# hot_spring.net
KiCad netlist of a schematic drawn in EAGLE
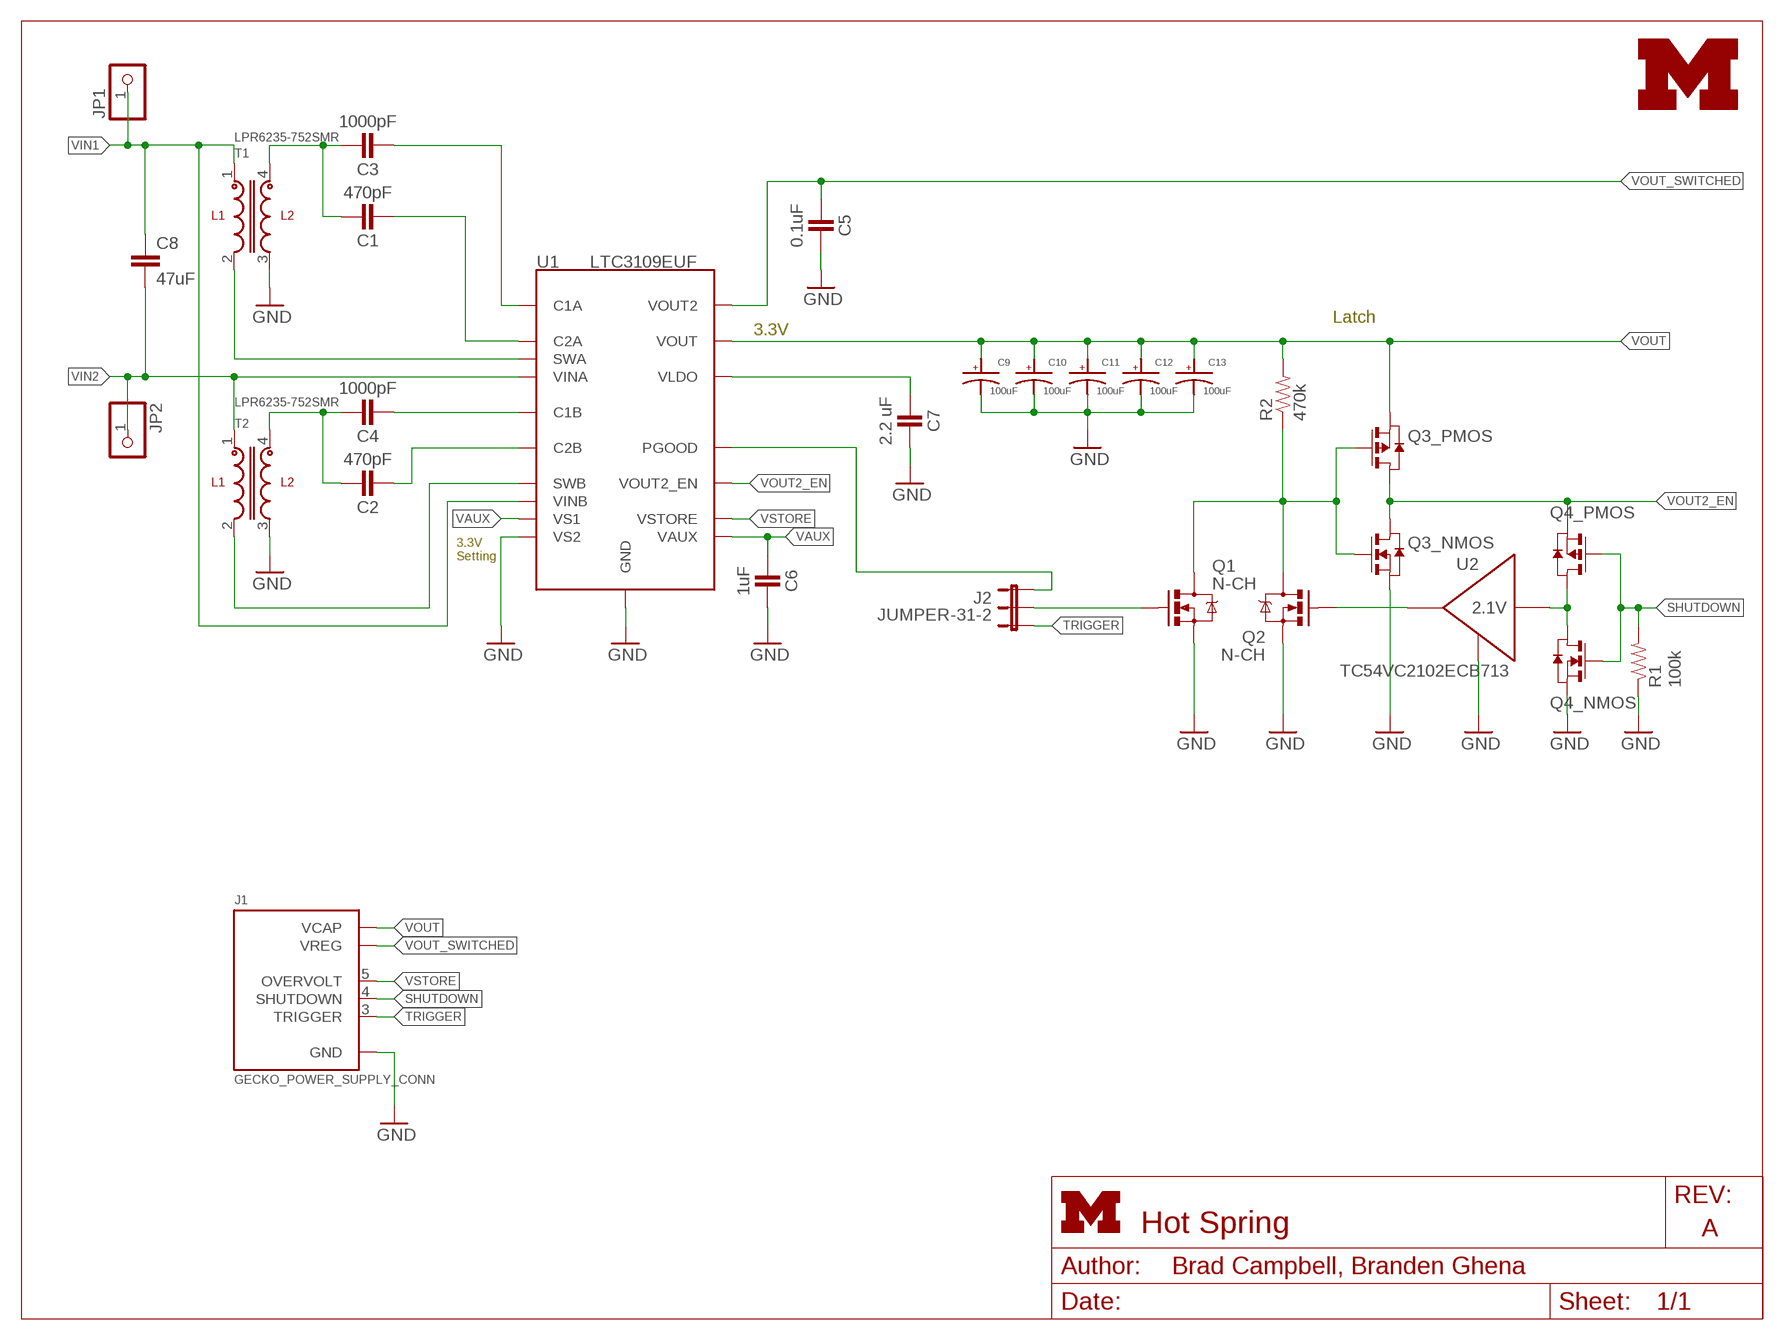
[diagram p0: schematic, sheet 1]

(export (version "E")
  (design (tool "Eeschema 10.0.6"))
  (components
    (comp (ref "C1")
      (value "470pF")
      (footprint "eagle-import:0402_CAP")
      (libsource (lib "eagle-import") (part "CAPACITOR"))
    )
    (comp (ref "C2")
      (value "470pF")
      (footprint "eagle-import:0402_CAP")
      (libsource (lib "eagle-import") (part "CAPACITOR"))
    )
    (comp (ref "C3")
      (value "1000pF")
      (footprint "eagle-import:0402_CAP")
      (libsource (lib "eagle-import") (part "CAPACITOR"))
    )
    (comp (ref "C4")
      (value "1000pF")
      (footprint "eagle-import:0402_CAP")
      (libsource (lib "eagle-import") (part "CAPACITOR"))
    )
    (comp (ref "C5")
      (value "0.1uF")
      (footprint "eagle-import:0402_CAP")
      (libsource (lib "eagle-import") (part "CAPACITOR"))
    )
    (comp (ref "C6")
      (value "1uF")
      (footprint "eagle-import:0402_CAP")
      (libsource (lib "eagle-import") (part "CAPACITOR"))
    )
    (comp (ref "C7")
      (value "2.2 uF")
      (footprint "eagle-import:0402_CAP")
      (libsource (lib "eagle-import") (part "CAPACITOR"))
    )
    (comp (ref "C8")
      (value "47uF")
      (footprint "eagle-import:1210")
      (libsource (lib "eagle-import") (part "CAP1210"))
    )
    (comp (ref "C9")
      (value "100uF")
      (footprint "eagle-import:CAP1210")
      (libsource (lib "eagle-import") (part "1210_CAP_POLARIZED"))
    )
    (comp (ref "C10")
      (value "100uF")
      (footprint "eagle-import:CAP1210")
      (libsource (lib "eagle-import") (part "1210_CAP_POLARIZED"))
    )
    (comp (ref "C11")
      (value "100uF")
      (footprint "eagle-import:CAP1210")
      (libsource (lib "eagle-import") (part "1210_CAP_POLARIZED"))
    )
    (comp (ref "C12")
      (value "100uF")
      (footprint "eagle-import:CAP1210")
      (libsource (lib "eagle-import") (part "1210_CAP_POLARIZED"))
    )
    (comp (ref "C13")
      (value "100uF")
      (footprint "eagle-import:CAP1210")
      (libsource (lib "eagle-import") (part "1210_CAP_POLARIZED"))
    )
    (comp (ref "J1")
      (value "GECKO_POWER_SUPPLY_CONN")
      (footprint "eagle-import:HEADER1X6_0.05IN")
      (libsource (lib "eagle-import") (part "GECKO_POWER_SUPPLY_CONN"))
    )
    (comp (ref "J2")
      (value "JUMPER-31-2")
      (footprint "eagle-import:SJ_3_PASTE1&2")
      (libsource (lib "eagle-import") (part "JUMPER-31-2"))
    )
    (comp (ref "JP1")
      (value "PINHD-1X1")
      (footprint "eagle-import:1X01")
      (libsource (lib "eagle-import") (part "PINHD-1X1"))
    )
    (comp (ref "JP2")
      (value "PINHD-1X1")
      (footprint "eagle-import:1X01")
      (libsource (lib "eagle-import") (part "PINHD-1X1"))
    )
    (comp (ref "LOGO1")
      (value "UMICH_SOLID_SMALL")
      (footprint "eagle-import:UMICH_SOLID_75MIL")
      (libsource (lib "eagle-import") (part "UMICH_SOLID_SMALL"))
    )
    (comp (ref "Q1")
      (value "MOSFET-NCHANNELSMD")
      (footprint "eagle-import:SOT23-3")
      (libsource (lib "eagle-import") (part "MOSFET-NCHANNELSMD"))
    )
    (comp (ref "Q2")
      (value "MOSFET-NCHANNELSMD")
      (footprint "eagle-import:SOT23-3")
      (libsource (lib "eagle-import") (part "MOSFET-NCHANNELSMD"))
    )
    (comp (ref "Q3")
      (value "DUAL_MOSFET_NP")
      (footprint "eagle-import:TSOP-6")
      (libsource (lib "eagle-import") (part "DUAL_MOSFET_NP"))
    )
    (comp (ref "Q4")
      (value "DUAL_MOSFET_NP")
      (footprint "eagle-import:TSOP-6")
      (libsource (lib "eagle-import") (part "DUAL_MOSFET_NP"))
    )
    (comp (ref "R1")
      (value "100k")
      (footprint "eagle-import:0402_RES")
      (libsource (lib "eagle-import") (part "RESISTOR0402_RES"))
    )
    (comp (ref "R2")
      (value "470k")
      (footprint "eagle-import:0402_RES")
      (libsource (lib "eagle-import") (part "RESISTOR0402_RES"))
    )
    (comp (ref "T1")
      (value "LPR6235-752SMR")
      (footprint "eagle-import:LPR6235")
      (libsource (lib "eagle-import") (part "LPR6235-752SMR"))
    )
    (comp (ref "T2")
      (value "LPR6235-752SMR")
      (footprint "eagle-import:LPR6235")
      (libsource (lib "eagle-import") (part "LPR6235-752SMR"))
    )
    (comp (ref "U1")
      (value "LTC3109EUF")
      (footprint "eagle-import:QFN-20-4MM")
      (libsource (lib "eagle-import") (part "LTC3109EUF"))
    )
    (comp (ref "U2")
      (value "TC54VC2102ECB713")
      (footprint "eagle-import:SOT-23")
      (libsource (lib "eagle-import") (part "TC54VC2102ECB713"))
    )
  )
  (nets
    (net (code "1") (name "GND") (class "Default")
      (node (ref "C10") (pin "ANODE") (pinfunction "ANODE_ANODE") (pintype "bidirectional"))
      (node (ref "C11") (pin "ANODE") (pinfunction "ANODE_ANODE") (pintype "bidirectional"))
      (node (ref "C12") (pin "ANODE") (pinfunction "ANODE_ANODE") (pintype "bidirectional"))
      (node (ref "C13") (pin "ANODE") (pinfunction "ANODE_ANODE") (pintype "bidirectional"))
      (node (ref "C5") (pin "1") (pinfunction "1_1") (pintype "bidirectional"))
      (node (ref "C6") (pin "1") (pinfunction "1_1") (pintype "bidirectional"))
      (node (ref "C7") (pin "1") (pinfunction "1_1") (pintype "bidirectional"))
      (node (ref "C9") (pin "ANODE") (pinfunction "ANODE_ANODE") (pintype "bidirectional"))
      (node (ref "J1") (pin "1") (pinfunction "GND_1") (pintype "bidirectional"))
      (node (ref "Q1") (pin "2") (pinfunction "S_2") (pintype "passive"))
      (node (ref "Q2") (pin "2") (pinfunction "S_2") (pintype "passive"))
      (node (ref "Q3") (pin "5") (pinfunction "S_5") (pintype "passive"))
      (node (ref "Q4") (pin "5") (pinfunction "S_5") (pintype "passive"))
      (node (ref "R1") (pin "1") (pinfunction "1_1") (pintype "passive"))
      (node (ref "T1") (pin "3") (pinfunction "3_3") (pintype "bidirectional"))
      (node (ref "T2") (pin "3") (pinfunction "3_3") (pintype "bidirectional"))
      (node (ref "U1") (pin "11") (pinfunction "GND_11") (pintype "bidirectional"))
      (node (ref "U1") (pin "16") (pinfunction "GND_16") (pintype "bidirectional"))
      (node (ref "U1") (pin "20") (pinfunction "VS2_20") (pintype "bidirectional"))
      (node (ref "U1") (pin "8") (pinfunction "GND_8") (pintype "bidirectional"))
      (node (ref "U1") (pin "GND") (pinfunction "GND_GND") (pintype "bidirectional"))
      (node (ref "U2") (pin "2") (pinfunction "GND_2") (pintype "bidirectional"))
    )
    (net (code "2") (name "Net-(C1-Pad1)") (class "Default")
      (node (ref "C1") (pin "1") (pinfunction "1_1") (pintype "bidirectional"))
      (node (ref "C3") (pin "1") (pinfunction "1_1") (pintype "bidirectional"))
      (node (ref "T1") (pin "4") (pinfunction "4_4") (pintype "bidirectional"))
    )
    (net (code "3") (name "Net-(C2-Pad1)") (class "Default")
      (node (ref "C2") (pin "1") (pinfunction "1_1") (pintype "bidirectional"))
      (node (ref "C4") (pin "1") (pinfunction "1_1") (pintype "bidirectional"))
      (node (ref "T2") (pin "4") (pinfunction "4_4") (pintype "bidirectional"))
    )
    (net (code "4") (name "Net-(Q1-D)") (class "Default")
      (node (ref "Q1") (pin "3") (pinfunction "D_3") (pintype "passive"))
      (node (ref "Q2") (pin "3") (pinfunction "D_3") (pintype "passive"))
      (node (ref "Q3") (pin "1") (pinfunction "G_1") (pintype "passive"))
      (node (ref "Q3") (pin "3") (pinfunction "G_3") (pintype "passive"))
      (node (ref "R2") (pin "1") (pinfunction "1_1") (pintype "passive"))
    )
    (net (code "5") (name "Net-(Q1-G)") (class "Default")
      (node (ref "J2") (pin "2") (pinfunction "2_2") (pintype "passive"))
      (node (ref "Q1") (pin "1") (pinfunction "G_1") (pintype "passive"))
    )
    (net (code "6") (name "Net-(Q2-G)") (class "Default")
      (node (ref "Q2") (pin "1") (pinfunction "G_1") (pintype "passive"))
      (node (ref "U2") (pin "1") (pinfunction "OUT_1") (pintype "bidirectional"))
    )
    (net (code "7") (name "Net-(Q4A-D)") (class "Default")
      (node (ref "Q4") (pin "4") (pinfunction "D_4") (pintype "passive"))
      (node (ref "Q4") (pin "6") (pinfunction "D_6") (pintype "passive"))
      (node (ref "U2") (pin "3") (pinfunction "IN_3") (pintype "bidirectional"))
    )
    (net (code "8") (name "Net-(U1-C1A)") (class "Default")
      (node (ref "C3") (pin "2") (pinfunction "2_2") (pintype "bidirectional"))
      (node (ref "U1") (pin "18") (pinfunction "C1A_18") (pintype "bidirectional"))
    )
    (net (code "9") (name "Net-(U1-C1B)") (class "Default")
      (node (ref "C4") (pin "2") (pinfunction "2_2") (pintype "bidirectional"))
      (node (ref "U1") (pin "9") (pinfunction "C1B_9") (pintype "bidirectional"))
    )
    (net (code "10") (name "Net-(U1-C2A)") (class "Default")
      (node (ref "C1") (pin "2") (pinfunction "2_2") (pintype "bidirectional"))
      (node (ref "U1") (pin "17") (pinfunction "C2A_17") (pintype "bidirectional"))
    )
    (net (code "11") (name "Net-(U1-C2B)") (class "Default")
      (node (ref "C2") (pin "2") (pinfunction "2_2") (pintype "bidirectional"))
      (node (ref "U1") (pin "10") (pinfunction "C2B_10") (pintype "bidirectional"))
    )
    (net (code "12") (name "Net-(U1-PGOOD)") (class "Default")
      (node (ref "J2") (pin "1") (pinfunction "1_1") (pintype "passive"))
      (node (ref "U1") (pin "6") (pinfunction "PGOOD_6") (pintype "bidirectional"))
    )
    (net (code "13") (name "Net-(U1-SWA)") (class "Default")
      (node (ref "T1") (pin "2") (pinfunction "2_2") (pintype "bidirectional"))
      (node (ref "U1") (pin "15") (pinfunction "SWA_15") (pintype "bidirectional"))
    )
    (net (code "14") (name "Net-(U1-SWB)") (class "Default")
      (node (ref "T2") (pin "2") (pinfunction "2_2") (pintype "bidirectional"))
      (node (ref "U1") (pin "12") (pinfunction "SWB_12") (pintype "bidirectional"))
    )
    (net (code "15") (name "Net-(U1-VLDO)") (class "Default")
      (node (ref "C7") (pin "2") (pinfunction "2_2") (pintype "bidirectional"))
      (node (ref "U1") (pin "7") (pinfunction "VLDO_7") (pintype "bidirectional"))
    )
    (net (code "16") (name "SHUTDOWN") (class "Default")
      (node (ref "J1") (pin "4") (pinfunction "SHUTDOWN_4") (pintype "bidirectional"))
      (node (ref "Q4") (pin "1") (pinfunction "G_1") (pintype "passive"))
      (node (ref "Q4") (pin "3") (pinfunction "G_3") (pintype "passive"))
      (node (ref "R1") (pin "2") (pinfunction "2_2") (pintype "passive"))
    )
    (net (code "17") (name "TRIGGER") (class "Default")
      (node (ref "J1") (pin "3") (pinfunction "TRIGGER_3") (pintype "bidirectional"))
      (node (ref "J2") (pin "3") (pinfunction "3_3") (pintype "passive"))
    )
    (net (code "18") (name "VAUX") (class "Default")
      (node (ref "C6") (pin "2") (pinfunction "2_2") (pintype "bidirectional"))
      (node (ref "U1") (pin "19") (pinfunction "VS1_19") (pintype "bidirectional"))
      (node (ref "U1") (pin "2") (pinfunction "VAUX_2") (pintype "bidirectional"))
    )
    (net (code "19") (name "VIN1") (class "Default")
      (node (ref "C8") (pin "1") (pinfunction "1_1") (pintype "passive"))
      (node (ref "JP1") (pin "1") (pinfunction "1_1") (pintype "passive"))
      (node (ref "T1") (pin "1") (pinfunction "1_1") (pintype "bidirectional"))
      (node (ref "U1") (pin "13") (pinfunction "VINB_13") (pintype "bidirectional"))
    )
    (net (code "20") (name "VIN2") (class "Default")
      (node (ref "C8") (pin "2") (pinfunction "2_2") (pintype "passive"))
      (node (ref "JP2") (pin "1") (pinfunction "1_1") (pintype "passive"))
      (node (ref "T2") (pin "1") (pinfunction "1_1") (pintype "bidirectional"))
      (node (ref "U1") (pin "14") (pinfunction "VINA_14") (pintype "bidirectional"))
    )
    (net (code "21") (name "VOUT") (class "Default")
      (node (ref "C10") (pin "CATHODE") (pinfunction "CATHODE_CATHODE") (pintype "bidirectional"))
      (node (ref "C11") (pin "CATHODE") (pinfunction "CATHODE_CATHODE") (pintype "bidirectional"))
      (node (ref "C12") (pin "CATHODE") (pinfunction "CATHODE_CATHODE") (pintype "bidirectional"))
      (node (ref "C13") (pin "CATHODE") (pinfunction "CATHODE_CATHODE") (pintype "bidirectional"))
      (node (ref "C9") (pin "CATHODE") (pinfunction "CATHODE_CATHODE") (pintype "bidirectional"))
      (node (ref "J1") (pin "6") (pinfunction "VCAP_6") (pintype "output"))
      (node (ref "Q3") (pin "2") (pinfunction "S_2") (pintype "passive"))
      (node (ref "R2") (pin "2") (pinfunction "2_2") (pintype "passive"))
      (node (ref "U1") (pin "3") (pinfunction "VOUT_3") (pintype "bidirectional"))
    )
    (net (code "22") (name "VOUT2_EN") (class "Default")
      (node (ref "Q3") (pin "4") (pinfunction "D_4") (pintype "passive"))
      (node (ref "Q3") (pin "6") (pinfunction "D_6") (pintype "passive"))
      (node (ref "Q4") (pin "2") (pinfunction "S_2") (pintype "passive"))
      (node (ref "U1") (pin "5") (pinfunction "VOUT2_EN_5") (pintype "bidirectional"))
    )
    (net (code "23") (name "VOUT_SWITCHED") (class "Default")
      (node (ref "C5") (pin "2") (pinfunction "2_2") (pintype "bidirectional"))
      (node (ref "J1") (pin "2") (pinfunction "VREG_2") (pintype "bidirectional"))
      (node (ref "U1") (pin "4") (pinfunction "VOUT2_4") (pintype "bidirectional"))
    )
    (net (code "24") (name "VSTORE") (class "Default")
      (node (ref "J1") (pin "5") (pinfunction "OVERVOLT_5") (pintype "bidirectional"))
      (node (ref "U1") (pin "1") (pinfunction "VSTORE_1") (pintype "bidirectional"))
    )
  )
)
